# 3_viper_eagle_modern_mcu.net
KiCad netlist of a schematic drawn in Altium Designer
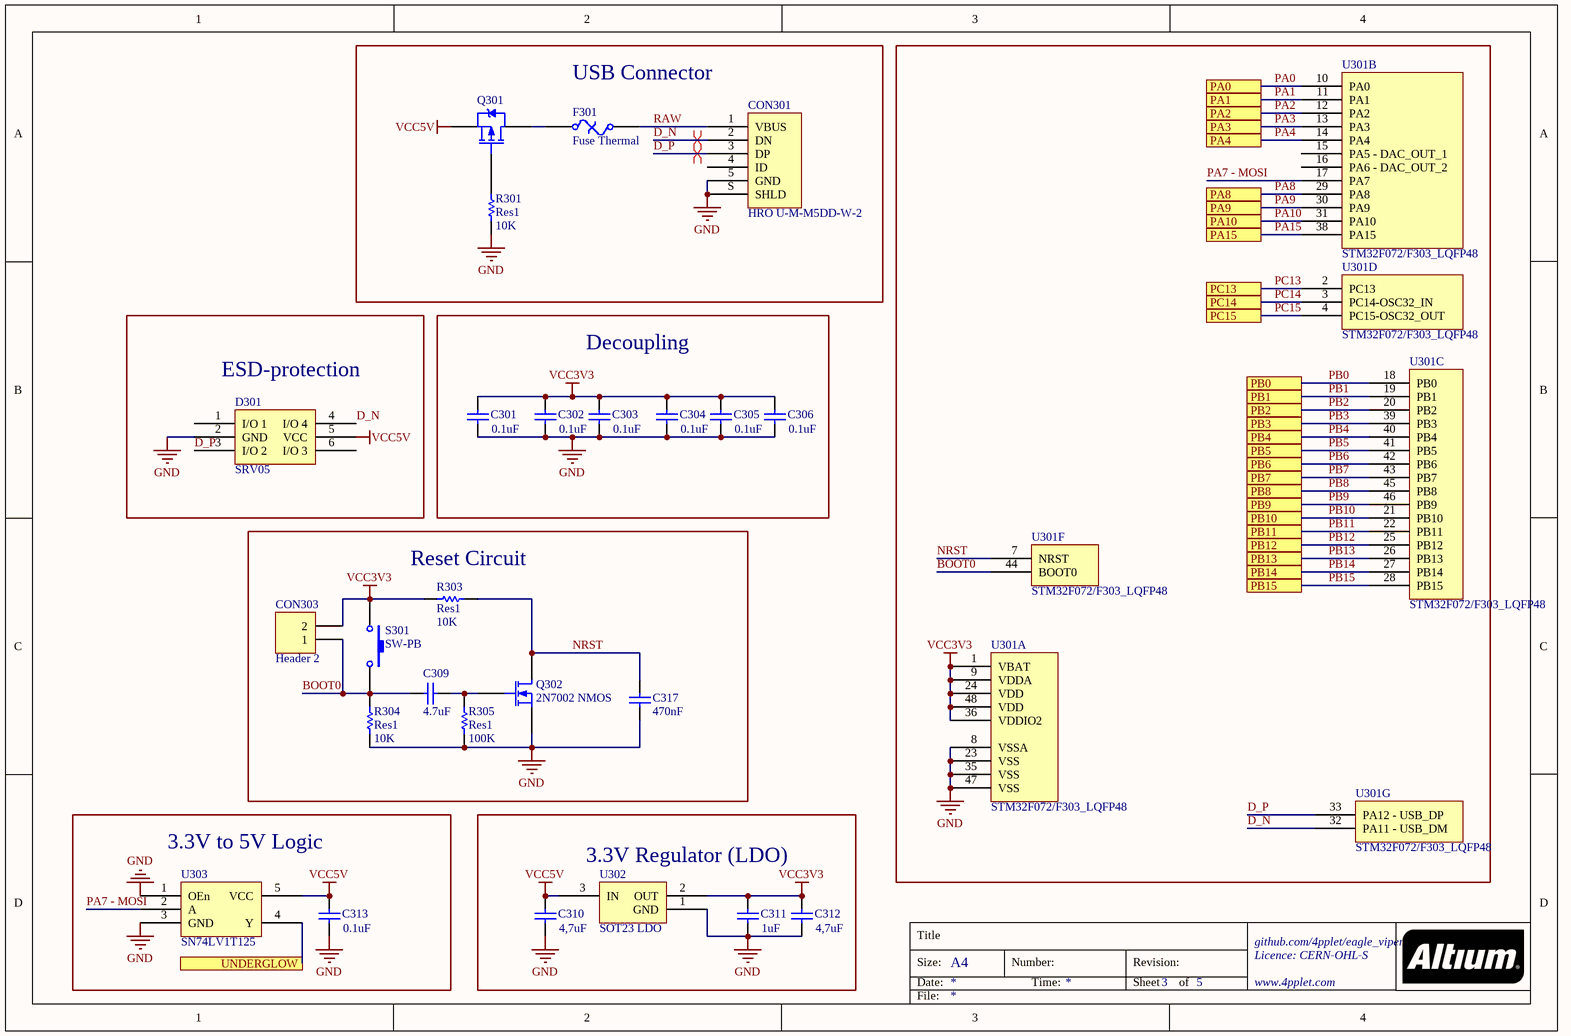
[diagram p0: 3_viper_eagle_modern_mcu.SchDoc]

(export (version "E")
  (design (tool "Eeschema 10.0.6"))
  (components
    (comp (ref "C301")
      (value "0.1uF")
      (footprint "C0603[1608]")
      (description "Capacitor")
      (fields (field (name "MFG") "KEMET") (field (name "LCSC PART #") "C14663"))
      (libsource (lib "Miscellaneous Devices") (part "Cap"))
    )
    (comp (ref "C302")
      (value "0.1uF")
      (footprint "C0603[1608]")
      (description "Capacitor")
      (fields (field (name "MFG") "KEMET") (field (name "LCSC PART #") "C14663"))
      (libsource (lib "Miscellaneous Devices") (part "Cap"))
    )
    (comp (ref "C303")
      (value "0.1uF")
      (footprint "C0603[1608]")
      (description "Capacitor")
      (fields (field (name "MFG") "KEMET") (field (name "LCSC PART #") "C14663"))
      (libsource (lib "Miscellaneous Devices") (part "Cap"))
    )
    (comp (ref "C304")
      (value "0.1uF")
      (footprint "C0603[1608]")
      (description "Capacitor")
      (fields (field (name "MFG") "KEMET") (field (name "LCSC PART #") "C14663"))
      (libsource (lib "Miscellaneous Devices") (part "Cap"))
    )
    (comp (ref "C305")
      (value "0.1uF")
      (footprint "C0603[1608]")
      (description "Capacitor")
      (fields (field (name "MFG") "KEMET") (field (name "LCSC PART #") "C14663"))
      (libsource (lib "Miscellaneous Devices") (part "Cap"))
    )
    (comp (ref "C306")
      (value "0.1uF")
      (footprint "C0603[1608]")
      (description "Capacitor")
      (fields (field (name "MFG") "KEMET") (field (name "LCSC PART #") "C14663"))
      (libsource (lib "Miscellaneous Devices") (part "Cap"))
    )
    (comp (ref "C309")
      (value "4.7uF")
      (footprint "C0603[1608]")
      (description "Capacitor")
      (fields (field (name "LCSC PART #") "C19666"))
      (libsource (lib "Miscellaneous Devices") (part "Cap"))
    )
    (comp (ref "C310")
      (value "4,7uF")
      (footprint "C0603[1608]")
      (description "Capacitor")
      (fields (field (name "LCSC PART #") "C19666"))
      (libsource (lib "Miscellaneous Devices") (part "Cap"))
    )
    (comp (ref "C311")
      (value "1uF")
      (footprint "C0603[1608]")
      (description "Capacitor")
      (fields (field (name "MFG") "KEMET") (field (name "LCSC PART #") "C15849"))
      (libsource (lib "Miscellaneous Devices") (part "Cap"))
    )
    (comp (ref "C312")
      (value "4,7uF")
      (footprint "C0603[1608]")
      (description "Capacitor")
      (fields (field (name "LCSC PART #") "C19666"))
      (libsource (lib "Miscellaneous Devices") (part "Cap"))
    )
    (comp (ref "C313")
      (value "0.1uF")
      (footprint "C0603[1608]")
      (description "Capacitor")
      (fields (field (name "MFG") "KEMET") (field (name "LCSC PART #") "C14663"))
      (libsource (lib "Miscellaneous Devices") (part "Cap"))
    )
    (comp (ref "C317")
      (value "470nF")
      (footprint "C0603[1608]")
      (description "Capacitor")
      (fields (field (name "MFG") "KEMET") (field (name "LCSC PART #") "C14663"))
      (libsource (lib "Miscellaneous Devices") (part "Cap"))
    )
    (comp (ref "CON301")
      (value "HRO U-M-M5DD-W-2")
      (footprint "HRO U-M-M5DD-W-2")
      (fields (field (name "LCSC PART #") "C879746") (field (name "MRF.PART") "U-M-M5DD-W-2"))
      (libsource (lib "Keebs") (part "HRO U-M-M5DD-W-2"))
    )
    (comp (ref "CON303")
      (value "Header 2")
      (footprint "HDR1X2")
      (description "Header, 2-Pin")
      (libsource (lib "Miscellaneous Connectors") (part "Header 2"))
    )
    (comp (ref "D301")
      (value "SRV05")
      (footprint "SOT-23-6")
      (fields (field (name "LCSC PART #") "C85364") (field (name "MRF.PART") "SRV05-4-P-T7"))
      (libsource (lib "Keebs") (part "SRV05"))
    )
    (comp (ref "F301")
      (value "Fuse Thermal")
      (footprint "C1206[3216]")
      (description "Thermal Fuse")
      (fields (field (name "MFG") "Bel Fuse Inc.") (field (name "LCSC PART #") "C135338"))
      (libsource (lib "Miscellaneous Devices") (part "Fuse Thermal"))
    )
    (comp (ref "Q301")
      (value "PMOS-2")
      (footprint "SOT-23-3")
      (description "P-Channel Power MOSFET")
      (fields (field (name "LCSC PART #") "C10487") (field (name "MRF.PART") "SI2301CDS-T1-GE3"))
      (libsource (lib "Miscellaneous Devices") (part "PMOS-2"))
    )
    (comp (ref "Q302")
      (value "2N7002 NMOS")
      (footprint "SOT-23-3")
      (description "N-Channel MOSFET")
      (fields (field (name "LCSC PART #") "C8545") (field (name "MRF.PART") "2N7002"))
      (libsource (lib "Miscellaneous Devices") (part "MOSFET-N"))
    )
    (comp (ref "R301")
      (value "Res1")
      (footprint "R0603[1608]")
      (description "Resistor")
      (fields
        (field (name "ALTIUM_VALUE") "10K")
        (field (name "MFG") "Panasonic Electronic Components")
        (field (name "LCSC PART #") "C25804")
      )
      (libsource (lib "Miscellaneous Devices") (part "Res1"))
    )
    (comp (ref "R303")
      (value "Res1")
      (footprint "R0603[1608]")
      (description "Resistor")
      (fields
        (field (name "ALTIUM_VALUE") "10K")
        (field (name "MFG") "Panasonic Electronic Components")
        (field (name "LCSC PART #") "C25804")
      )
      (libsource (lib "Miscellaneous Devices") (part "Res1"))
    )
    (comp (ref "R304")
      (value "Res1")
      (footprint "R0603[1608]")
      (description "Resistor")
      (fields
        (field (name "ALTIUM_VALUE") "10K")
        (field (name "MFG") "Panasonic Electronic Components")
        (field (name "LCSC PART #") "C25804")
      )
      (libsource (lib "Miscellaneous Devices") (part "Res1"))
    )
    (comp (ref "R305")
      (value "Res1")
      (footprint "R0603[1608]")
      (description "Resistor")
      (fields
        (field (name "ALTIUM_VALUE") "100K")
        (field (name "LCSC PART #") "C25803")
        (field (name "MRF.PART") "0603WAF1003T5E")
      )
      (libsource (lib "Miscellaneous Devices") (part "Res1"))
    )
    (comp (ref "S301")
      (value "SW-PB")
      (footprint "XKB Switch")
      (description "Switch")
      (fields (field (name "MFG") "C&K") (field (name "MRF.PART") "TS-1187A-C-D-B"))
      (libsource (lib "Miscellaneous Devices") (part "SW-PB"))
    )
    (comp (ref "U301")
      (value "STM32F072/F303_LQFP48")
      (footprint "STM32 - COMBO 7X7MM")
      (fields (field (name "LCSC PART #") "C92504") (field (name "MRF.PART") "STM32F072CBU6"))
      (libsource (lib "Keebs") (part "STM32F072/F303_LQFP48"))
    )
    (comp (ref "U302")
      (value "SOT23 LDO")
      (footprint "SOT-23-3")
      (fields
        (field (name "LCSC PART #") "C5446")
        (field (name "MRF.PART") "XC6206P332MR")
        (field (name "MFG") "Texas Instruments")
      )
      (libsource (lib "Keebs") (part "SOT23 LDO"))
    )
    (comp (ref "U303")
      (value "SN74LV1T125")
      (footprint "SOT-23-5")
      (description "SN74LV1T125 or SN74LV1T34. Connect OE to GND")
      (fields (field (name "LCSC PART #") "C473338") (field (name "MRF.PART") "SN74LV1T125DBVR"))
      (libsource (lib "Keebs") (part "SN74LV1T125"))
    )
  )
  (nets
    (net (code "1") (name "/BOOT0") (class "Default")
      (node (ref "C309") (pin "1") (pinfunction "1_1") (pintype "passive"))
      (node (ref "CON303") (pin "1") (pinfunction "1_1") (pintype "passive"))
      (node (ref "R304") (pin "1") (pinfunction "1_1") (pintype "passive"))
      (node (ref "S301") (pin "2") (pinfunction "2_2") (pintype "passive"))
      (node (ref "U301") (pin "44") (pinfunction "BOOT0_44") (pintype "passive"))
    )
    (net (code "2") (name "/D_N") (class "Default")
      (node (ref "CON301") (pin "2") (pinfunction "DN_2") (pintype "passive"))
      (node (ref "D301") (pin "4") (pinfunction "I/O_4_4") (pintype "passive"))
      (node (ref "U301") (pin "32") (pinfunction "PA11_-_USB_DM_32") (pintype "passive"))
    )
    (net (code "3") (name "/D_P") (class "Default")
      (node (ref "CON301") (pin "3") (pinfunction "DP_3") (pintype "passive"))
      (node (ref "D301") (pin "3") (pinfunction "I/O_2_3") (pintype "passive"))
      (node (ref "U301") (pin "33") (pinfunction "PA12_-_USB_DP_33") (pintype "passive"))
    )
    (net (code "4") (name "/NRST") (class "Default")
      (node (ref "C317") (pin "1") (pinfunction "1_1") (pintype "passive"))
      (node (ref "Q302") (pin "3") (pinfunction "D_3") (pintype "passive"))
      (node (ref "R303") (pin "2") (pinfunction "2_2") (pintype "passive"))
      (node (ref "U301") (pin "7") (pinfunction "NRST_7") (pintype "passive"))
    )
    (net (code "5") (name "/PA0") (class "Default")
      (node (ref "U301") (pin "10") (pinfunction "PA0_10") (pintype "passive"))
    )
    (net (code "6") (name "/PA1") (class "Default")
      (node (ref "U301") (pin "11") (pinfunction "PA1_11") (pintype "passive"))
    )
    (net (code "7") (name "/PA2") (class "Default")
      (node (ref "U301") (pin "12") (pinfunction "PA2_12") (pintype "passive"))
    )
    (net (code "8") (name "/PA3") (class "Default")
      (node (ref "U301") (pin "13") (pinfunction "PA3_13") (pintype "passive"))
    )
    (net (code "9") (name "/PA4") (class "Default")
      (node (ref "U301") (pin "14") (pinfunction "PA4_14") (pintype "passive"))
    )
    (net (code "10") (name "/PA7 - MOSI") (class "Default")
      (node (ref "U301") (pin "17") (pinfunction "PA7_17") (pintype "passive"))
      (node (ref "U303") (pin "2") (pinfunction "A_2") (pintype "passive"))
    )
    (net (code "11") (name "/PA8") (class "Default")
      (node (ref "U301") (pin "29") (pinfunction "PA8_29") (pintype "passive"))
    )
    (net (code "12") (name "/PA9") (class "Default")
      (node (ref "U301") (pin "30") (pinfunction "PA9_30") (pintype "passive"))
    )
    (net (code "13") (name "/PA10") (class "Default")
      (node (ref "U301") (pin "31") (pinfunction "PA10_31") (pintype "passive"))
    )
    (net (code "14") (name "/PA15") (class "Default")
      (node (ref "U301") (pin "38") (pinfunction "PA15_38") (pintype "passive"))
    )
    (net (code "15") (name "/PB0") (class "Default")
      (node (ref "U301") (pin "18") (pinfunction "PB0_18") (pintype "passive"))
    )
    (net (code "16") (name "/PB1") (class "Default")
      (node (ref "U301") (pin "19") (pinfunction "PB1_19") (pintype "passive"))
    )
    (net (code "17") (name "/PB2") (class "Default")
      (node (ref "U301") (pin "20") (pinfunction "PB2_20") (pintype "passive"))
    )
    (net (code "18") (name "/PB3") (class "Default")
      (node (ref "U301") (pin "39") (pinfunction "PB3_39") (pintype "passive"))
    )
    (net (code "19") (name "/PB4") (class "Default")
      (node (ref "U301") (pin "40") (pinfunction "PB4_40") (pintype "passive"))
    )
    (net (code "20") (name "/PB5") (class "Default")
      (node (ref "U301") (pin "41") (pinfunction "PB5_41") (pintype "passive"))
    )
    (net (code "21") (name "/PB6") (class "Default")
      (node (ref "U301") (pin "42") (pinfunction "PB6_42") (pintype "passive"))
    )
    (net (code "22") (name "/PB7") (class "Default")
      (node (ref "U301") (pin "43") (pinfunction "PB7_43") (pintype "passive"))
    )
    (net (code "23") (name "/PB8") (class "Default")
      (node (ref "U301") (pin "45") (pinfunction "PB8_45") (pintype "passive"))
    )
    (net (code "24") (name "/PB9") (class "Default")
      (node (ref "U301") (pin "46") (pinfunction "PB9_46") (pintype "passive"))
    )
    (net (code "25") (name "/PB10") (class "Default")
      (node (ref "U301") (pin "21") (pinfunction "PB10_21") (pintype "passive"))
    )
    (net (code "26") (name "/PB11") (class "Default")
      (node (ref "U301") (pin "22") (pinfunction "PB11_22") (pintype "passive"))
    )
    (net (code "27") (name "/PB12") (class "Default")
      (node (ref "U301") (pin "25") (pinfunction "PB12_25") (pintype "passive"))
    )
    (net (code "28") (name "/PB13") (class "Default")
      (node (ref "U301") (pin "26") (pinfunction "PB13_26") (pintype "passive"))
    )
    (net (code "29") (name "/PB14") (class "Default")
      (node (ref "U301") (pin "27") (pinfunction "PB14_27") (pintype "passive"))
    )
    (net (code "30") (name "/PB15") (class "Default")
      (node (ref "U301") (pin "28") (pinfunction "PB15_28") (pintype "passive"))
    )
    (net (code "31") (name "/PC13") (class "Default")
      (node (ref "U301") (pin "2") (pinfunction "PC13_2") (pintype "passive"))
    )
    (net (code "32") (name "/PC14") (class "Default")
      (node (ref "U301") (pin "3") (pinfunction "PC14-OSC32_IN_3") (pintype "passive"))
    )
    (net (code "33") (name "/PC15") (class "Default")
      (node (ref "U301") (pin "4") (pinfunction "PC15-OSC32_OUT_4") (pintype "passive"))
    )
    (net (code "34") (name "/RAW") (class "Default")
      (node (ref "CON301") (pin "1") (pinfunction "VBUS_1") (pintype "passive"))
      (node (ref "F301") (pin "2") (pinfunction "2_2") (pintype "passive"))
    )
    (net (code "35") (name "/UNDERGLOW") (class "Default")
      (node (ref "U303") (pin "4") (pinfunction "Y_4") (pintype "passive"))
    )
    (net (code "36") (name "GND") (class "Default")
      (node (ref "C301") (pin "1") (pinfunction "1_1") (pintype "passive"))
      (node (ref "C302") (pin "1") (pinfunction "1_1") (pintype "passive"))
      (node (ref "C303") (pin "1") (pinfunction "1_1") (pintype "passive"))
      (node (ref "C304") (pin "1") (pinfunction "1_1") (pintype "passive"))
      (node (ref "C305") (pin "1") (pinfunction "1_1") (pintype "passive"))
      (node (ref "C306") (pin "1") (pinfunction "1_1") (pintype "passive"))
      (node (ref "C310") (pin "1") (pinfunction "1_1") (pintype "passive"))
      (node (ref "C311") (pin "1") (pinfunction "1_1") (pintype "passive"))
      (node (ref "C312") (pin "1") (pinfunction "1_1") (pintype "passive"))
      (node (ref "C313") (pin "1") (pinfunction "1_1") (pintype "passive"))
      (node (ref "C317") (pin "2") (pinfunction "2_2") (pintype "passive"))
      (node (ref "CON301") (pin "5") (pinfunction "GND_5") (pintype "passive"))
      (node (ref "CON301") (pin "S") (pinfunction "SHLD_S") (pintype "passive"))
      (node (ref "D301") (pin "2") (pinfunction "GND_2") (pintype "passive"))
      (node (ref "Q302") (pin "2") (pinfunction "S_2") (pintype "passive"))
      (node (ref "R301") (pin "2") (pinfunction "2_2") (pintype "passive"))
      (node (ref "R304") (pin "2") (pinfunction "2_2") (pintype "passive"))
      (node (ref "R305") (pin "2") (pinfunction "2_2") (pintype "passive"))
      (node (ref "U301") (pin "23") (pinfunction "VSS_23") (pintype "passive"))
      (node (ref "U301") (pin "35") (pinfunction "VSS_35") (pintype "passive"))
      (node (ref "U301") (pin "47") (pinfunction "VSS_47") (pintype "passive"))
      (node (ref "U301") (pin "8") (pinfunction "VSSA_8") (pintype "passive"))
      (node (ref "U302") (pin "1") (pinfunction "GND_1") (pintype "passive"))
      (node (ref "U303") (pin "1") (pinfunction "OEn_1") (pintype "passive"))
      (node (ref "U303") (pin "3") (pinfunction "GND_3") (pintype "passive"))
    )
    (net (code "37") (name "Net-(Q301-D)") (class "Default")
      (node (ref "F301") (pin "1") (pinfunction "1_1") (pintype "passive"))
      (node (ref "Q301") (pin "3") (pinfunction "D_3") (pintype "passive"))
    )
    (net (code "38") (name "Net-(Q301-G)") (class "Default")
      (node (ref "Q301") (pin "1") (pinfunction "G_1") (pintype "passive"))
      (node (ref "R301") (pin "1") (pinfunction "1_1") (pintype "passive"))
    )
    (net (code "39") (name "Net-(Q302-G)") (class "Default")
      (node (ref "C309") (pin "2") (pinfunction "2_2") (pintype "passive"))
      (node (ref "Q302") (pin "1") (pinfunction "G_1") (pintype "passive"))
      (node (ref "R305") (pin "1") (pinfunction "1_1") (pintype "passive"))
    )
    (net (code "40") (name "VCC3V3") (class "Default")
      (node (ref "C301") (pin "2") (pinfunction "2_2") (pintype "passive"))
      (node (ref "C302") (pin "2") (pinfunction "2_2") (pintype "passive"))
      (node (ref "C303") (pin "2") (pinfunction "2_2") (pintype "passive"))
      (node (ref "C304") (pin "2") (pinfunction "2_2") (pintype "passive"))
      (node (ref "C305") (pin "2") (pinfunction "2_2") (pintype "passive"))
      (node (ref "C306") (pin "2") (pinfunction "2_2") (pintype "passive"))
      (node (ref "C311") (pin "2") (pinfunction "2_2") (pintype "passive"))
      (node (ref "C312") (pin "2") (pinfunction "2_2") (pintype "passive"))
      (node (ref "CON303") (pin "2") (pinfunction "2_2") (pintype "passive"))
      (node (ref "R303") (pin "1") (pinfunction "1_1") (pintype "passive"))
      (node (ref "S301") (pin "1") (pinfunction "1_1") (pintype "passive"))
      (node (ref "U301") (pin "1") (pinfunction "VBAT_1") (pintype "passive"))
      (node (ref "U301") (pin "24") (pinfunction "VDD_24") (pintype "passive"))
      (node (ref "U301") (pin "36") (pinfunction "VDDIO2_36") (pintype "passive"))
      (node (ref "U301") (pin "48") (pinfunction "VDD_48") (pintype "passive"))
      (node (ref "U301") (pin "9") (pinfunction "VDDA_9") (pintype "passive"))
      (node (ref "U302") (pin "2") (pinfunction "OUT_2") (pintype "passive"))
    )
    (net (code "41") (name "VCC5V") (class "Default")
      (node (ref "C310") (pin "2") (pinfunction "2_2") (pintype "passive"))
      (node (ref "C313") (pin "2") (pinfunction "2_2") (pintype "passive"))
      (node (ref "D301") (pin "5") (pinfunction "VCC_5") (pintype "passive"))
      (node (ref "Q301") (pin "2") (pinfunction "S_2") (pintype "passive"))
      (node (ref "U302") (pin "3") (pinfunction "IN_3") (pintype "passive"))
      (node (ref "U303") (pin "5") (pinfunction "VCC_5") (pintype "passive"))
    )
    (net (code "42") (name "unconnected-(CON301-ID-Pad4)") (class "Default")
      (node (ref "CON301") (pin "4") (pinfunction "ID_4") (pintype "passive"))
    )
    (net (code "43") (name "unconnected-(D301-I{slash}O_1-Pad1)") (class "Default")
      (node (ref "D301") (pin "1") (pinfunction "I/O_1_1") (pintype "passive"))
    )
    (net (code "44") (name "unconnected-(D301-I{slash}O_3-Pad6)") (class "Default")
      (node (ref "D301") (pin "6") (pinfunction "I/O_3_6") (pintype "passive"))
    )
    (net (code "45") (name "unconnected-(U301B-PA5_-_DAC_OUT_1-Pad15)") (class "Default")
      (node (ref "U301") (pin "15") (pinfunction "PA5_-_DAC_OUT_1_15") (pintype "passive"))
    )
    (net (code "46") (name "unconnected-(U301B-PA6_-_DAC_OUT_2-Pad16)") (class "Default")
      (node (ref "U301") (pin "16") (pinfunction "PA6_-_DAC_OUT_2_16") (pintype "passive"))
    )
  )
)
